# ADC_PWM_Board.net
KiCad netlist of a schematic drawn in EAGLE
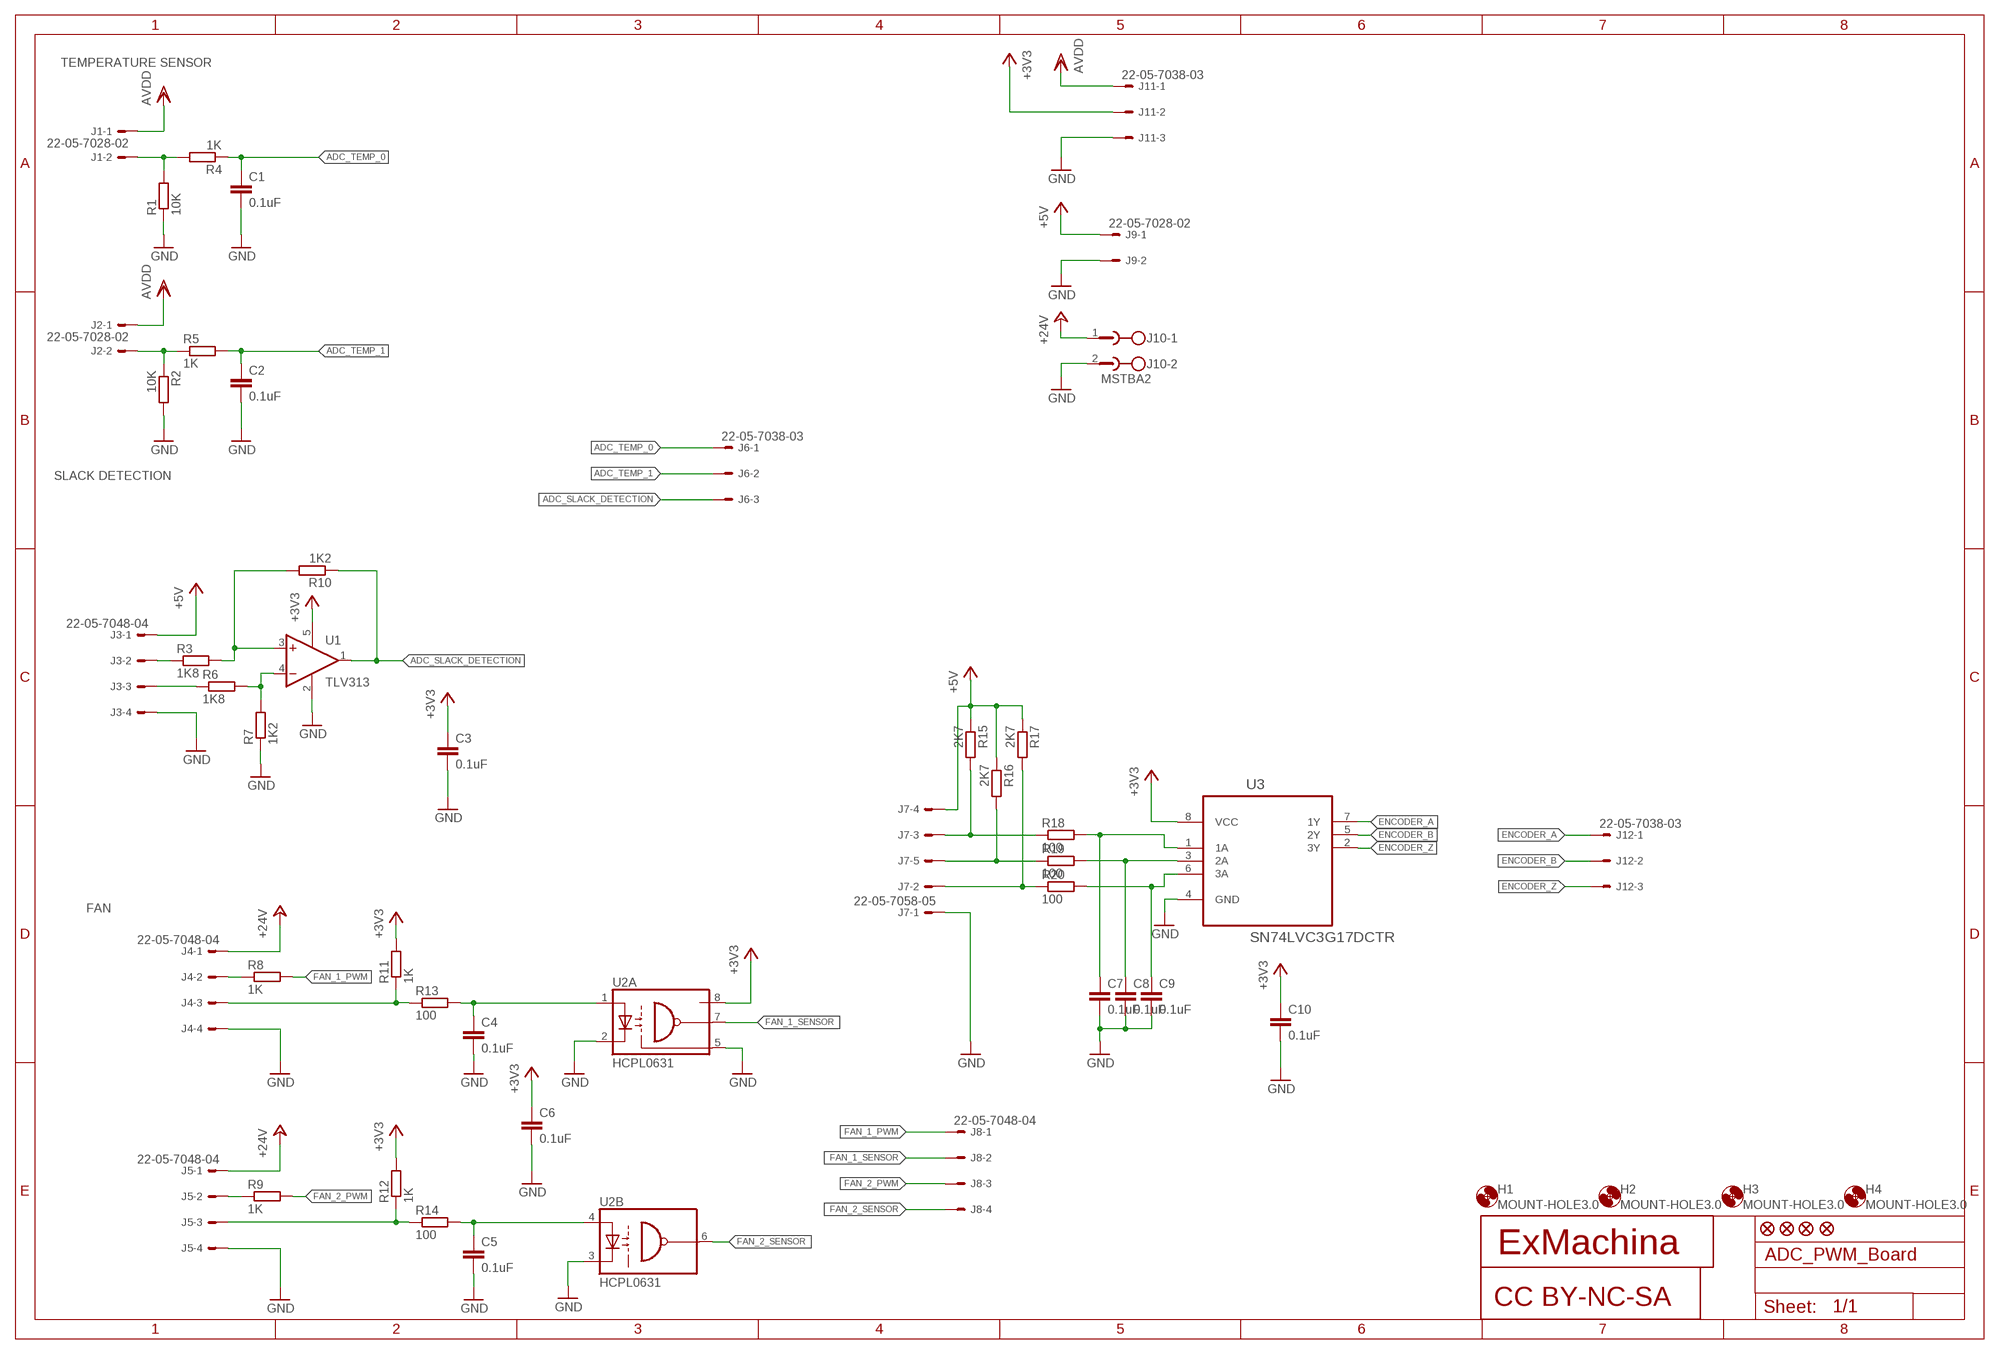
[diagram p0: schematic, sheet 1]

(export (version "E")
  (design (tool "Eeschema 10.0.6"))
  (components
    (comp (ref "C1")
      (value "0.1uF")
      (footprint "eagle-import:C0603")
      (fields (field (name "MPN") "MC0603B104K250CT"))
      (libsource (lib "eagle-import") (part "C-EUC0603"))
    )
    (comp (ref "C2")
      (value "0.1uF")
      (footprint "eagle-import:C0603")
      (fields (field (name "MPN") "MC0603B104K250CT"))
      (libsource (lib "eagle-import") (part "C-EUC0603"))
    )
    (comp (ref "C3")
      (value "0.1uF")
      (footprint "eagle-import:C0603")
      (fields (field (name "MPN") "MC0603B104K250CT"))
      (libsource (lib "eagle-import") (part "C-EUC0603"))
    )
    (comp (ref "C4")
      (value "0.1uF")
      (footprint "eagle-import:C0603")
      (fields (field (name "MPN") "MC0603B104K250CT"))
      (libsource (lib "eagle-import") (part "C-EUC0603"))
    )
    (comp (ref "C5")
      (value "0.1uF")
      (footprint "eagle-import:C0603")
      (fields (field (name "MPN") "MC0603B104K250CT"))
      (libsource (lib "eagle-import") (part "C-EUC0603"))
    )
    (comp (ref "C6")
      (value "0.1uF")
      (footprint "eagle-import:C0603")
      (fields (field (name "MPN") "MC0603B104K250CT"))
      (libsource (lib "eagle-import") (part "C-EUC0603"))
    )
    (comp (ref "C7")
      (value "0.1uF")
      (footprint "eagle-import:C0603")
      (fields (field (name "MPN") "MC0603B104K250CT"))
      (libsource (lib "eagle-import") (part "C-EUC0603"))
    )
    (comp (ref "C8")
      (value "0.1uF")
      (footprint "eagle-import:C0603")
      (fields (field (name "MPN") "MC0603B104K250CT"))
      (libsource (lib "eagle-import") (part "C-EUC0603"))
    )
    (comp (ref "C9")
      (value "0.1uF")
      (footprint "eagle-import:C0603")
      (fields (field (name "MPN") "MC0603B104K250CT"))
      (libsource (lib "eagle-import") (part "C-EUC0603"))
    )
    (comp (ref "C10")
      (value "0.1uF")
      (footprint "eagle-import:C0603")
      (fields (field (name "MPN") "MC0603B104K250CT"))
      (libsource (lib "eagle-import") (part "C-EUC0603"))
    )
    (comp (ref "CC1")
      (value "CC-BY-NC-SA")
      (footprint "eagle-import:CC-BY-NC-SA")
      (libsource (lib "eagle-import") (part "CC-BY-NC-SA"))
    )
    (comp (ref "H1")
      (value "MOUNT-HOLE3.0")
      (footprint "eagle-import:3,0")
      (libsource (lib "eagle-import") (part "MOUNT-HOLE3.0"))
    )
    (comp (ref "H2")
      (value "MOUNT-HOLE3.0")
      (footprint "eagle-import:3,0")
      (libsource (lib "eagle-import") (part "MOUNT-HOLE3.0"))
    )
    (comp (ref "H3")
      (value "MOUNT-HOLE3.0")
      (footprint "eagle-import:3,0")
      (libsource (lib "eagle-import") (part "MOUNT-HOLE3.0"))
    )
    (comp (ref "H4")
      (value "MOUNT-HOLE3.0")
      (footprint "eagle-import:3,0")
      (libsource (lib "eagle-import") (part "MOUNT-HOLE3.0"))
    )
    (comp (ref "J1")
      (value "22-05-7028-02")
      (footprint "eagle-import:7395-02")
      (fields (field (name "MPN") "22-05-7028") (field (name "OC_NEWARK") "25M1728"))
      (libsource (lib "eagle-import") (part "22-?-0205-7028"))
    )
    (comp (ref "J2")
      (value "22-05-7028-02")
      (footprint "eagle-import:7395-02")
      (fields (field (name "MPN") "22-05-7028") (field (name "OC_NEWARK") "25M1728"))
      (libsource (lib "eagle-import") (part "22-?-0205-7028"))
    )
    (comp (ref "J3")
      (value "22-05-7048-04")
      (footprint "eagle-import:7395-04")
      (fields (field (name "MPN") "22-05-7048") (field (name "OC_NEWARK") "26M6363"))
      (libsource (lib "eagle-import") (part "22-?-0405-7048"))
    )
    (comp (ref "J4")
      (value "22-05-7048-04")
      (footprint "eagle-import:7395-04")
      (fields (field (name "MPN") "22-05-7048") (field (name "OC_NEWARK") "26M6363"))
      (libsource (lib "eagle-import") (part "22-?-0405-7048"))
    )
    (comp (ref "J5")
      (value "22-05-7048-04")
      (footprint "eagle-import:7395-04")
      (fields (field (name "MPN") "22-05-7048") (field (name "OC_NEWARK") "26M6363"))
      (libsource (lib "eagle-import") (part "22-?-0405-7048"))
    )
    (comp (ref "J6")
      (value "22-05-7038-03")
      (footprint "eagle-import:7395-03")
      (fields (field (name "MPN") "22-05-7038") (field (name "OC_NEWARK") "26M6362"))
      (libsource (lib "eagle-import") (part "22-?-0305-7038"))
    )
    (comp (ref "J7")
      (value "22-05-7058-05")
      (footprint "eagle-import:7395-05")
      (fields
        (field (name "MF") "MOLEX")
        (field (name "MPN") "22-05-7058")
        (field (name "OC_NEWARK") "55H9619")
      )
      (libsource (lib "eagle-import") (part "22-?-0505-7058"))
    )
    (comp (ref "J8")
      (value "22-05-7048-04")
      (footprint "eagle-import:7395-04")
      (fields (field (name "MPN") "22-05-7048") (field (name "OC_NEWARK") "26M6363"))
      (libsource (lib "eagle-import") (part "22-?-0405-7048"))
    )
    (comp (ref "J9")
      (value "22-05-7028-02")
      (footprint "eagle-import:7395-02")
      (fields (field (name "MPN") "22-05-7028") (field (name "OC_NEWARK") "25M1728"))
      (libsource (lib "eagle-import") (part "22-?-0205-7028"))
    )
    (comp (ref "J10")
      (value "MSTBA2")
      (footprint "eagle-import:MSTBA2")
      (fields (field (name "MF") "FARNELL") (field (name "MPN") "1757242"))
      (libsource (lib "eagle-import") (part "MSTBA2"))
    )
    (comp (ref "J11")
      (value "22-05-7038-03")
      (footprint "eagle-import:7395-03")
      (fields (field (name "MPN") "22-05-7038") (field (name "OC_NEWARK") "26M6362"))
      (libsource (lib "eagle-import") (part "22-?-0305-7038"))
    )
    (comp (ref "J12")
      (value "22-05-7038-03")
      (footprint "eagle-import:7395-03")
      (fields (field (name "MPN") "22-05-7038") (field (name "OC_NEWARK") "26M6362"))
      (libsource (lib "eagle-import") (part "22-?-0305-7038"))
    )
    (comp (ref "JP1")
      (value "FIDUCIAL1X2")
      (footprint "eagle-import:FIDUCIAL-1X2")
      (libsource (lib "eagle-import") (part "FIDUCIAL1X2"))
    )
    (comp (ref "JP2")
      (value "FIDUCIAL1X2")
      (footprint "eagle-import:FIDUCIAL-1X2")
      (libsource (lib "eagle-import") (part "FIDUCIAL1X2"))
    )
    (comp (ref "JP3")
      (value "FIDUCIAL1X2")
      (footprint "eagle-import:FIDUCIAL-1X2")
      (libsource (lib "eagle-import") (part "FIDUCIAL1X2"))
    )
    (comp (ref "JP4")
      (value "FIDUCIAL1X2")
      (footprint "eagle-import:FIDUCIAL-1X2")
      (libsource (lib "eagle-import") (part "FIDUCIAL1X2"))
    )
    (comp (ref "R1")
      (value "10K")
      (footprint "eagle-import:R0603")
      (fields (field (name "MPN") "MCMR06X1002FTL"))
      (libsource (lib "eagle-import") (part "R-EU_R0603"))
    )
    (comp (ref "R2")
      (value "10K")
      (footprint "eagle-import:R0603")
      (fields (field (name "MPN") "MCMR06X1002FTL"))
      (libsource (lib "eagle-import") (part "R-EU_R0603"))
    )
    (comp (ref "R3")
      (value "1K8")
      (footprint "eagle-import:R0603")
      (fields (field (name "MPN") "MCMR06X1801FTL"))
      (libsource (lib "eagle-import") (part "R-EU_R0603"))
    )
    (comp (ref "R4")
      (value "1K")
      (footprint "eagle-import:R0603")
      (fields (field (name "MPN") "MCMR06X1001FTL"))
      (libsource (lib "eagle-import") (part "R-EU_R0603"))
    )
    (comp (ref "R5")
      (value "1K")
      (footprint "eagle-import:R0603")
      (fields (field (name "MPN") "MCMR06X1001FTL"))
      (libsource (lib "eagle-import") (part "R-EU_R0603"))
    )
    (comp (ref "R6")
      (value "1K8")
      (footprint "eagle-import:R0603")
      (fields (field (name "MPN") "MCMR06X1801FTL"))
      (libsource (lib "eagle-import") (part "R-EU_R0603"))
    )
    (comp (ref "R7")
      (value "1K2")
      (footprint "eagle-import:R0603")
      (fields (field (name "MPN") "MCMR06X1201FTL"))
      (libsource (lib "eagle-import") (part "R-EU_R0603"))
    )
    (comp (ref "R8")
      (value "1K")
      (footprint "eagle-import:R0603")
      (fields (field (name "MPN") "MCMR06X1001FTL"))
      (libsource (lib "eagle-import") (part "R-EU_R0603"))
    )
    (comp (ref "R9")
      (value "1K")
      (footprint "eagle-import:R0603")
      (fields (field (name "MPN") "MCMR06X1001FTL"))
      (libsource (lib "eagle-import") (part "R-EU_R0603"))
    )
    (comp (ref "R10")
      (value "1K2")
      (footprint "eagle-import:R0603")
      (fields (field (name "MPN") "MCMR06X1201FTL"))
      (libsource (lib "eagle-import") (part "R-EU_R0603"))
    )
    (comp (ref "R11")
      (value "1K")
      (footprint "eagle-import:R0603")
      (fields (field (name "MPN") "MCMR06X1001FTL"))
      (libsource (lib "eagle-import") (part "R-EU_R0603"))
    )
    (comp (ref "R12")
      (value "1K")
      (footprint "eagle-import:R0603")
      (fields (field (name "MPN") "MCMR06X1001FTL"))
      (libsource (lib "eagle-import") (part "R-EU_R0603"))
    )
    (comp (ref "R13")
      (value "100")
      (footprint "eagle-import:R0603")
      (fields (field (name "MPN") "MCMR06X1000FTL"))
      (libsource (lib "eagle-import") (part "R-EU_R0603"))
    )
    (comp (ref "R14")
      (value "100")
      (footprint "eagle-import:R0603")
      (fields (field (name "MPN") "MCMR06X1000FTL"))
      (libsource (lib "eagle-import") (part "R-EU_R0603"))
    )
    (comp (ref "R15")
      (value "2K7")
      (footprint "eagle-import:R0603")
      (fields (field (name "MPN") "MCMR06X4701FTL"))
      (libsource (lib "eagle-import") (part "R-EU_R0603"))
    )
    (comp (ref "R16")
      (value "2K7")
      (footprint "eagle-import:R0603")
      (fields (field (name "MPN") "MCMR06X4701FTL"))
      (libsource (lib "eagle-import") (part "R-EU_R0603"))
    )
    (comp (ref "R17")
      (value "2K7")
      (footprint "eagle-import:R0603")
      (fields (field (name "MPN") "MCMR06X4701FTL"))
      (libsource (lib "eagle-import") (part "R-EU_R0603"))
    )
    (comp (ref "R18")
      (value "100")
      (footprint "eagle-import:R0603")
      (fields (field (name "MPN") "MCMR06X1000FTL"))
      (libsource (lib "eagle-import") (part "R-EU_R0603"))
    )
    (comp (ref "R19")
      (value "100")
      (footprint "eagle-import:R0603")
      (fields (field (name "MPN") "MCMR06X1000FTL"))
      (libsource (lib "eagle-import") (part "R-EU_R0603"))
    )
    (comp (ref "R20")
      (value "100")
      (footprint "eagle-import:R0603")
      (fields (field (name "MPN") "MCMR06X1000FTL"))
      (libsource (lib "eagle-import") (part "R-EU_R0603"))
    )
    (comp (ref "T1")
      (value "EXMACHINA-LOGO-NAME")
      (footprint "eagle-import:EXM-LOGO-BASELINE")
      (libsource (lib "eagle-import") (part "EXMACHINA-LOGO-NAME"))
    )
    (comp (ref "U1")
      (value "TLV313")
      (footprint "eagle-import:SOT23-DBV")
      (fields (field (name "MPN") "TLV313IDBVT"))
      (libsource (lib "eagle-import") (part "TLV313"))
    )
    (comp (ref "U2")
      (value "HCPL0631")
      (footprint "eagle-import:SOIC08")
      (fields (field (name "MPN") "HCPL-0631-500E") (field (name "OC_NEWARK") "52M7944"))
      (libsource (lib "eagle-import") (part "HCPL0631"))
    )
    (comp (ref "U3")
      (value "SN74LVC3G17DCTR")
      (footprint "eagle-import:SOP65P400X130-8N")
      (fields (field (name "MF") "TEXAS INSTRUMENTS"))
      (libsource (lib "eagle-import") (part "SN74LVC3G17DCTR"))
    )
  )
  (nets
    (net (code "1") (name "+3V3") (class "Default")
      (node (ref "C10") (pin "1") (pinfunction "1_1") (pintype "passive"))
      (node (ref "C3") (pin "1") (pinfunction "1_1") (pintype "passive"))
      (node (ref "C6") (pin "1") (pinfunction "1_1") (pintype "passive"))
      (node (ref "J11") (pin "2") (pinfunction "S_2") (pintype "passive"))
      (node (ref "R11") (pin "2") (pinfunction "2_2") (pintype "passive"))
      (node (ref "R12") (pin "2") (pinfunction "2_2") (pintype "passive"))
      (node (ref "U1") (pin "5") (pinfunction "V+_5") (pintype "power_in"))
      (node (ref "U2") (pin "8") (pinfunction "VCC_8") (pintype "power_in"))
      (node (ref "U3") (pin "8") (pinfunction "VCC_8") (pintype "power_in"))
    )
    (net (code "2") (name "+5V") (class "Default")
      (node (ref "J3") (pin "1") (pinfunction "S_1") (pintype "passive"))
      (node (ref "J7") (pin "4") (pinfunction "S_4") (pintype "passive"))
      (node (ref "J9") (pin "1") (pinfunction "S_1") (pintype "passive"))
      (node (ref "R15") (pin "1") (pinfunction "1_1") (pintype "passive"))
      (node (ref "R16") (pin "1") (pinfunction "1_1") (pintype "passive"))
      (node (ref "R17") (pin "1") (pinfunction "1_1") (pintype "passive"))
    )
    (net (code "3") (name "+24V") (class "Default")
      (node (ref "J10") (pin "1") (pinfunction "1_1") (pintype "passive"))
      (node (ref "J4") (pin "1") (pinfunction "S_1") (pintype "passive"))
      (node (ref "J5") (pin "1") (pinfunction "S_1") (pintype "passive"))
    )
    (net (code "4") (name "ADC_SLACK_DETECTION") (class "Default")
      (node (ref "J6") (pin "3") (pinfunction "S_3") (pintype "passive"))
      (node (ref "R10") (pin "1") (pinfunction "1_1") (pintype "passive"))
      (node (ref "U1") (pin "1") (pinfunction "OUT_1") (pintype "output"))
    )
    (net (code "5") (name "ADC_TEMP_0") (class "Default")
      (node (ref "C1") (pin "1") (pinfunction "1_1") (pintype "passive"))
      (node (ref "J6") (pin "1") (pinfunction "S_1") (pintype "passive"))
      (node (ref "R4") (pin "1") (pinfunction "1_1") (pintype "passive"))
    )
    (net (code "6") (name "ADC_TEMP_1") (class "Default")
      (node (ref "C2") (pin "1") (pinfunction "1_1") (pintype "passive"))
      (node (ref "J6") (pin "2") (pinfunction "S_2") (pintype "passive"))
      (node (ref "R5") (pin "2") (pinfunction "2_2") (pintype "passive"))
    )
    (net (code "7") (name "AVDD") (class "Default")
      (node (ref "J1") (pin "1") (pinfunction "S_1") (pintype "passive"))
      (node (ref "J11") (pin "1") (pinfunction "S_1") (pintype "passive"))
      (node (ref "J2") (pin "1") (pinfunction "S_1") (pintype "passive"))
    )
    (net (code "8") (name "ENCODER_A") (class "Default")
      (node (ref "J12") (pin "1") (pinfunction "S_1") (pintype "passive"))
      (node (ref "U3") (pin "7") (pinfunction "1Y_7") (pintype "output"))
    )
    (net (code "9") (name "ENCODER_B") (class "Default")
      (node (ref "J12") (pin "2") (pinfunction "S_2") (pintype "passive"))
      (node (ref "U3") (pin "5") (pinfunction "2Y_5") (pintype "output"))
    )
    (net (code "10") (name "ENCODER_Z") (class "Default")
      (node (ref "J12") (pin "3") (pinfunction "S_3") (pintype "passive"))
      (node (ref "U3") (pin "2") (pinfunction "3Y_2") (pintype "output"))
    )
    (net (code "11") (name "FAN_1_PWM") (class "Default")
      (node (ref "J8") (pin "1") (pinfunction "S_1") (pintype "passive"))
      (node (ref "R8") (pin "2") (pinfunction "2_2") (pintype "passive"))
    )
    (net (code "12") (name "FAN_1_SENSOR") (class "Default")
      (node (ref "J8") (pin "2") (pinfunction "S_2") (pintype "passive"))
      (node (ref "U2") (pin "7") (pinfunction "VO_7") (pintype "passive"))
    )
    (net (code "13") (name "FAN_2_PWM") (class "Default")
      (node (ref "J8") (pin "3") (pinfunction "S_3") (pintype "passive"))
      (node (ref "R9") (pin "2") (pinfunction "2_2") (pintype "passive"))
    )
    (net (code "14") (name "FAN_2_SENSOR") (class "Default")
      (node (ref "J8") (pin "4") (pinfunction "S_4") (pintype "passive"))
      (node (ref "U2") (pin "6") (pinfunction "VO2_6") (pintype "passive"))
    )
    (net (code "15") (name "GND") (class "Default")
      (node (ref "C1") (pin "2") (pinfunction "2_2") (pintype "passive"))
      (node (ref "C10") (pin "2") (pinfunction "2_2") (pintype "passive"))
      (node (ref "C2") (pin "2") (pinfunction "2_2") (pintype "passive"))
      (node (ref "C3") (pin "2") (pinfunction "2_2") (pintype "passive"))
      (node (ref "C4") (pin "2") (pinfunction "2_2") (pintype "passive"))
      (node (ref "C5") (pin "2") (pinfunction "2_2") (pintype "passive"))
      (node (ref "C6") (pin "2") (pinfunction "2_2") (pintype "passive"))
      (node (ref "C7") (pin "2") (pinfunction "2_2") (pintype "passive"))
      (node (ref "C8") (pin "2") (pinfunction "2_2") (pintype "passive"))
      (node (ref "C9") (pin "2") (pinfunction "2_2") (pintype "passive"))
      (node (ref "J10") (pin "2") (pinfunction "1_2") (pintype "passive"))
      (node (ref "J11") (pin "3") (pinfunction "S_3") (pintype "passive"))
      (node (ref "J3") (pin "4") (pinfunction "S_4") (pintype "passive"))
      (node (ref "J4") (pin "4") (pinfunction "S_4") (pintype "passive"))
      (node (ref "J5") (pin "4") (pinfunction "S_4") (pintype "passive"))
      (node (ref "J7") (pin "1") (pinfunction "S_1") (pintype "passive"))
      (node (ref "J9") (pin "2") (pinfunction "S_2") (pintype "passive"))
      (node (ref "R1") (pin "1") (pinfunction "1_1") (pintype "passive"))
      (node (ref "R2") (pin "2") (pinfunction "2_2") (pintype "passive"))
      (node (ref "R7") (pin "1") (pinfunction "1_1") (pintype "passive"))
      (node (ref "U1") (pin "2") (pinfunction "V-_2") (pintype "power_in"))
      (node (ref "U2") (pin "2") (pinfunction "C1_2") (pintype "passive"))
      (node (ref "U2") (pin "3") (pinfunction "C2_3") (pintype "passive"))
      (node (ref "U2") (pin "5") (pinfunction "GND_5") (pintype "passive"))
      (node (ref "U3") (pin "4") (pinfunction "GND_4") (pintype "passive"))
    )
    (net (code "16") (name "Net-(J1B-S)") (class "Default")
      (node (ref "J1") (pin "2") (pinfunction "S_2") (pintype "passive"))
      (node (ref "R1") (pin "2") (pinfunction "2_2") (pintype "passive"))
      (node (ref "R4") (pin "2") (pinfunction "2_2") (pintype "passive"))
    )
    (net (code "17") (name "Net-(J2B-S)") (class "Default")
      (node (ref "J2") (pin "2") (pinfunction "S_2") (pintype "passive"))
      (node (ref "R2") (pin "1") (pinfunction "1_1") (pintype "passive"))
      (node (ref "R5") (pin "1") (pinfunction "1_1") (pintype "passive"))
    )
    (net (code "18") (name "Net-(J3B-S)") (class "Default")
      (node (ref "J3") (pin "2") (pinfunction "S_2") (pintype "passive"))
      (node (ref "R3") (pin "1") (pinfunction "1_1") (pintype "passive"))
    )
    (net (code "19") (name "Net-(J3C-S)") (class "Default")
      (node (ref "J3") (pin "3") (pinfunction "S_3") (pintype "passive"))
      (node (ref "R6") (pin "1") (pinfunction "1_1") (pintype "passive"))
    )
    (net (code "20") (name "Net-(J4B-S)") (class "Default")
      (node (ref "J4") (pin "2") (pinfunction "S_2") (pintype "passive"))
      (node (ref "R8") (pin "1") (pinfunction "1_1") (pintype "passive"))
    )
    (net (code "21") (name "Net-(J4C-S)") (class "Default")
      (node (ref "J4") (pin "3") (pinfunction "S_3") (pintype "passive"))
      (node (ref "R11") (pin "1") (pinfunction "1_1") (pintype "passive"))
      (node (ref "R13") (pin "1") (pinfunction "1_1") (pintype "passive"))
    )
    (net (code "22") (name "Net-(J5B-S)") (class "Default")
      (node (ref "J5") (pin "2") (pinfunction "S_2") (pintype "passive"))
      (node (ref "R9") (pin "1") (pinfunction "1_1") (pintype "passive"))
    )
    (net (code "23") (name "Net-(J5C-S)") (class "Default")
      (node (ref "J5") (pin "3") (pinfunction "S_3") (pintype "passive"))
      (node (ref "R12") (pin "1") (pinfunction "1_1") (pintype "passive"))
      (node (ref "R14") (pin "1") (pinfunction "1_1") (pintype "passive"))
    )
    (net (code "24") (name "Net-(J7B-S)") (class "Default")
      (node (ref "J7") (pin "2") (pinfunction "S_2") (pintype "passive"))
      (node (ref "R17") (pin "2") (pinfunction "2_2") (pintype "passive"))
      (node (ref "R20") (pin "1") (pinfunction "1_1") (pintype "passive"))
    )
    (net (code "25") (name "Net-(J7C-S)") (class "Default")
      (node (ref "J7") (pin "3") (pinfunction "S_3") (pintype "passive"))
      (node (ref "R15") (pin "2") (pinfunction "2_2") (pintype "passive"))
      (node (ref "R18") (pin "1") (pinfunction "1_1") (pintype "passive"))
    )
    (net (code "26") (name "Net-(J7E-S)") (class "Default")
      (node (ref "J7") (pin "5") (pinfunction "S_5") (pintype "passive"))
      (node (ref "R16") (pin "2") (pinfunction "2_2") (pintype "passive"))
      (node (ref "R19") (pin "1") (pinfunction "1_1") (pintype "passive"))
    )
    (net (code "27") (name "Net-(U1-+IN)") (class "Default")
      (node (ref "R10") (pin "2") (pinfunction "2_2") (pintype "passive"))
      (node (ref "R3") (pin "2") (pinfunction "2_2") (pintype "passive"))
      (node (ref "U1") (pin "3") (pinfunction "+IN_3") (pintype "input"))
    )
    (net (code "28") (name "Net-(U1--IN)") (class "Default")
      (node (ref "R6") (pin "2") (pinfunction "2_2") (pintype "passive"))
      (node (ref "R7") (pin "2") (pinfunction "2_2") (pintype "passive"))
      (node (ref "U1") (pin "4") (pinfunction "-IN_4") (pintype "input"))
    )
    (net (code "29") (name "Net-(U2A-A1)") (class "Default")
      (node (ref "C4") (pin "1") (pinfunction "1_1") (pintype "passive"))
      (node (ref "R13") (pin "2") (pinfunction "2_2") (pintype "passive"))
      (node (ref "U2") (pin "1") (pinfunction "A1_1") (pintype "passive"))
    )
    (net (code "30") (name "Net-(U2B-A2)") (class "Default")
      (node (ref "C5") (pin "1") (pinfunction "1_1") (pintype "passive"))
      (node (ref "R14") (pin "2") (pinfunction "2_2") (pintype "passive"))
      (node (ref "U2") (pin "4") (pinfunction "A2_4") (pintype "passive"))
    )
    (net (code "31") (name "Net-(U3-1A)") (class "Default")
      (node (ref "C7") (pin "1") (pinfunction "1_1") (pintype "passive"))
      (node (ref "R18") (pin "2") (pinfunction "2_2") (pintype "passive"))
      (node (ref "U3") (pin "1") (pinfunction "1A_1") (pintype "input"))
    )
    (net (code "32") (name "Net-(U3-2A)") (class "Default")
      (node (ref "C8") (pin "1") (pinfunction "1_1") (pintype "passive"))
      (node (ref "R19") (pin "2") (pinfunction "2_2") (pintype "passive"))
      (node (ref "U3") (pin "3") (pinfunction "2A_3") (pintype "input"))
    )
    (net (code "33") (name "Net-(U3-3A)") (class "Default")
      (node (ref "C9") (pin "1") (pinfunction "1_1") (pintype "passive"))
      (node (ref "R20") (pin "2") (pinfunction "2_2") (pintype "passive"))
      (node (ref "U3") (pin "6") (pinfunction "3A_6") (pintype "input"))
    )
  )
)
